# Schematic.net
KiCad netlist of a schematic drawn in Altium Designer
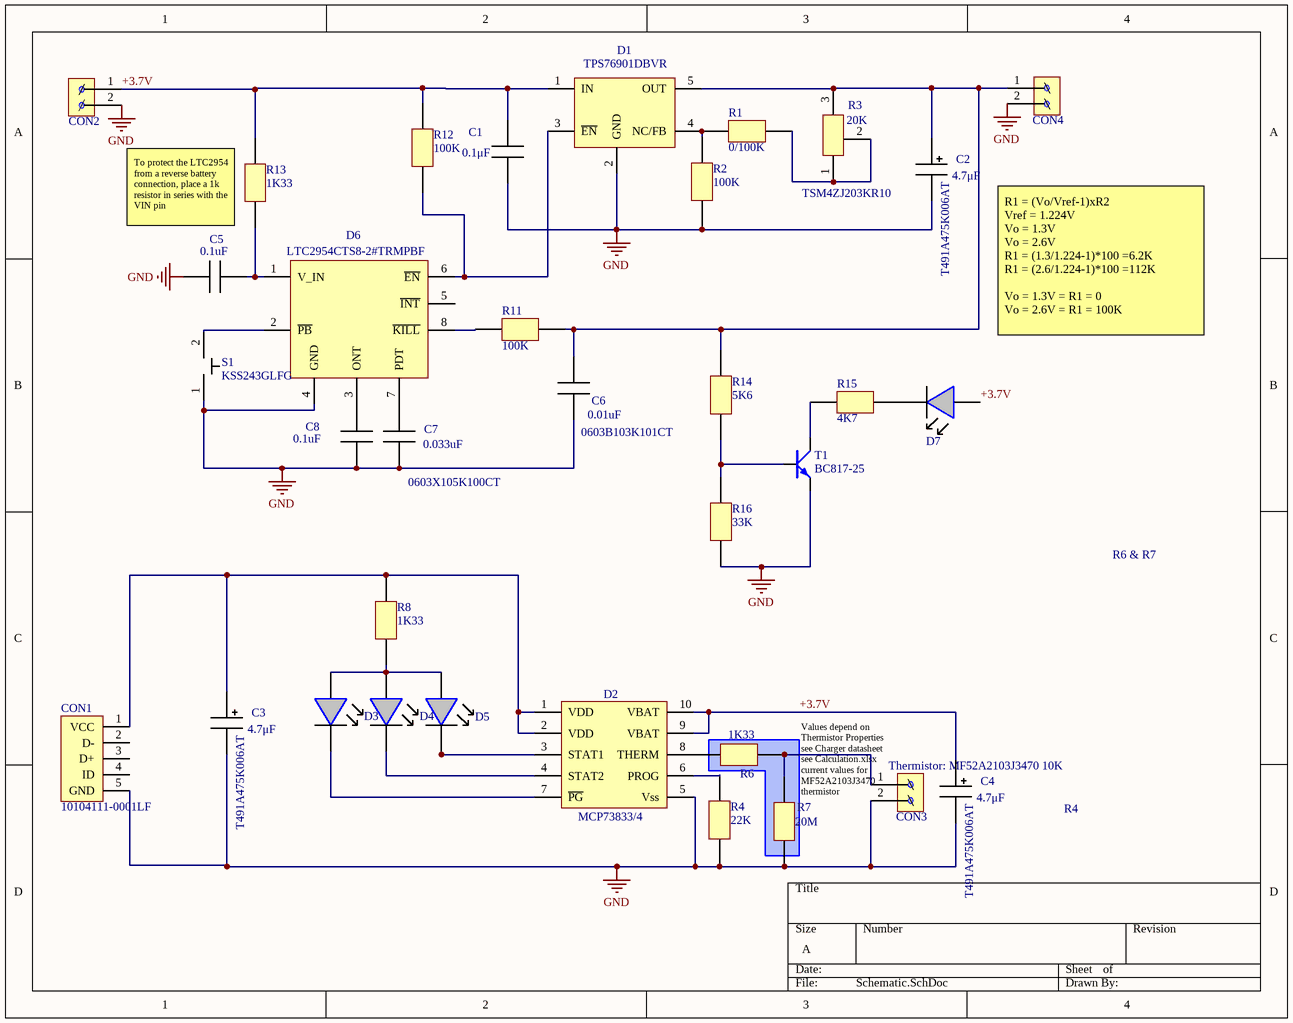
[diagram p0: Schematic.SchDoc]

(export (version "E")
  (design (tool "Eeschema 10.0.6"))
  (components
    (comp (ref "C1")
      (value "Capasitor")
      (footprint "CAPC1608X05N")
      (fields (field (name "CAPASITANCE") "0.1μF"))
      (libsource (lib "Componets") (part "Capasitor"))
    )
    (comp (ref "C2")
      (value "Capasitor_POL")
      (footprint "CAPMP3216X18N")
      (fields
        (field (name "CAPASITANCE") "4.7μF")
        (field (name "MANUFACTURER") "KEMET")
        (field (name "MANUFACTURERPN") "T491A475K006AT")
      )
      (libsource (lib "Componets") (part "Capasitor_POL"))
    )
    (comp (ref "C3")
      (value "Capasitor_POL")
      (footprint "CAPMP3216X18N")
      (fields
        (field (name "CAPASITANCE") "4.7μF")
        (field (name "MANUFACTURER") "KEMET")
        (field (name "MANUFACTURERPN") "T491A475K006AT")
      )
      (libsource (lib "Componets") (part "Capasitor_POL"))
    )
    (comp (ref "C4")
      (value "Capasitor_POL")
      (footprint "CAPMP3216X18N")
      (fields
        (field (name "CAPASITANCE") "4.7μF")
        (field (name "MANUFACTURER") "KEMET")
        (field (name "MANUFACTURERPN") "T491A475K006AT")
      )
      (libsource (lib "Componets") (part "Capasitor_POL"))
    )
    (comp (ref "C5")
      (value "Capasitor")
      (footprint "CAPC1608X05N")
      (fields (field (name "CAPASITANCE") "0.1uF"))
      (libsource (lib "Componets") (part "Capasitor"))
    )
    (comp (ref "C6")
      (value "Capasitor")
      (footprint "CAPC1608X05N")
      (fields
        (field (name "CAPASITANCE") "0.01uF")
        (field (name "MANUFACTURER") "WALSIN")
        (field (name "MANUFACTURERPN") "0603B103K101CT")
      )
      (libsource (lib "Componets") (part "Capasitor"))
    )
    (comp (ref "C7")
      (value "Capasitor")
      (footprint "CAPC1608X05N")
      (fields
        (field (name "CAPASITANCE") "0.033uF")
        (field (name "MANUFACTURER") "WALSIN")
        (field (name "MANUFACTURERPN") "0603X105K100CT")
      )
      (libsource (lib "Componets") (part "Capasitor"))
    )
    (comp (ref "C8")
      (value "Capasitor")
      (footprint "CAPC1608X05N")
      (fields (field (name "CAPASITANCE") "0.1uF"))
      (libsource (lib "Componets") (part "Capasitor"))
    )
    (comp (ref "CON1")
      (value "CON?")
      (footprint "MicroUSB")
      (fields (field (name "MANUFACTURER") "AMPHENOL FCI") (field (name "PARTNUMBER") "10104111-0001LF"))
      (libsource (lib "Componets") (part "MicroUSB"))
    )
    (comp (ref "CON2")
      (value "CON?")
      (footprint "HDR1X2_no_body")
      (libsource (lib "Componets") (part "HDR1X2"))
    )
    (comp (ref "CON3")
      (value "CON?")
      (footprint "HDR1X2_no_body")
      (fields (field (name "THERMISTOR") "MF52A2103J3470 10K"))
      (libsource (lib "") (part "HDR1X2_1"))
    )
    (comp (ref "CON4") (value "CON?") (footprint "HDR1X2_no_body") (libsource (lib "") (part "HDR1X2_1")))
    (comp (ref "D1")
      (value "D?")
      (footprint "SOT23-5AN")
      (fields (field (name "PARTNUMBER") "TPS76901DBVR"))
      (libsource (lib "Componets") (part "TPS76901"))
    )
    (comp (ref "D2")
      (value "MCP73833/4")
      (footprint "TSSOP50P490-10AN")
      (libsource (lib "Componets") (part "MCP73833/4"))
    )
    (comp (ref "D3") (value "LED") (footprint "CD1608-0603") (libsource (lib "Componets") (part "LED")))
    (comp (ref "D4") (value "LED") (footprint "CD1608-0603") (libsource (lib "Componets") (part "LED")))
    (comp (ref "D5") (value "LED") (footprint "CD1608-0603") (libsource (lib "Componets") (part "LED")))
    (comp (ref "D6")
      (value "D?")
      (footprint "TSOP65P280X100-8N")
      (fields (field (name "TEXASINSTRUMENTS") "LTC2954CTS8-2#TRMPBF"))
      (libsource (lib "Componets") (part "LTC2654-2"))
    )
    (comp (ref "D7") (value "LED") (footprint "CD1608-0603") (libsource (lib "Componets") (part "LED")))
    (comp (ref "R1")
      (value "R?")
      (footprint "RESC1608X04N")
      (fields (field (name "RESISTANCE") "0/100K"))
      (libsource (lib "") (part "Resistor_1"))
    )
    (comp (ref "R2")
      (value "R?")
      (footprint "RESC1608X04N")
      (fields (field (name "RESISTANCE") "100K"))
      (libsource (lib "Componets") (part "Resistor"))
    )
    (comp (ref "R3")
      (value "R?")
      (footprint "TSM4ZJ")
      (fields
        (field (name "RESISTANCE") "20K")
        (field (name "PARTNUMBER") "TSM4ZJ203KR10")
        (field (name "MANUFACTURER") "VISHAY")
      )
      (libsource (lib "Componets") (part "Resistor_ADJ"))
    )
    (comp (ref "R4")
      (value "R?")
      (footprint "RESC1608X04N")
      (fields (field (name "RESISTANCE") "22K"))
      (libsource (lib "Componets") (part "Resistor"))
    )
    (comp (ref "R6")
      (value "R?")
      (footprint "RESC1608X04N")
      (fields (field (name "RESISTANCE") "1K33"))
      (libsource (lib "") (part "Resistor_1"))
    )
    (comp (ref "R7")
      (value "R?")
      (footprint "RESC1608X04N")
      (fields (field (name "RESISTANCE") "20M"))
      (libsource (lib "Componets") (part "Resistor"))
    )
    (comp (ref "R8")
      (value "R?")
      (footprint "RESC1608X04N")
      (fields (field (name "RESISTANCE") "1K33"))
      (libsource (lib "Componets") (part "Resistor"))
    )
    (comp (ref "R11")
      (value "R?")
      (footprint "RESC1608X04N")
      (fields (field (name "RESISTANCE") "100K"))
      (libsource (lib "") (part "Resistor_1"))
    )
    (comp (ref "R12")
      (value "R?")
      (footprint "RESC1608X04N")
      (fields (field (name "RESISTANCE") "100K"))
      (libsource (lib "Componets") (part "Resistor"))
    )
    (comp (ref "R13")
      (value "R?")
      (footprint "RESC1608X04N")
      (fields (field (name "RESISTANCE") "1K33"))
      (libsource (lib "Componets") (part "Resistor"))
    )
    (comp (ref "R14")
      (value "R?")
      (footprint "RESC1608X04N")
      (fields (field (name "RESISTANCE") "5K6"))
      (libsource (lib "Componets") (part "Resistor"))
    )
    (comp (ref "R15")
      (value "R?")
      (footprint "RESC1608X04N")
      (fields (field (name "RESISTANCE") "4K7"))
      (libsource (lib "") (part "Resistor_1"))
    )
    (comp (ref "R16")
      (value "R?")
      (footprint "RESC1608X04N")
      (fields (field (name "RESISTANCE") "33K"))
      (libsource (lib "Componets") (part "Resistor"))
    )
    (comp (ref "S1")
      (value "S?")
      (footprint "KSS241")
      (fields (field (name "MANUFACTURER") "C and K components") (field (name "MANUFACTURERPN") "KSS243GLFG"))
      (libsource (lib "Componets") (part "PushButton"))
    )
    (comp (ref "T1")
      (value "BC817-25")
      (footprint "SOT323-3AM")
      (libsource (lib "Componets") (part "NPN SMD"))
    )
  )
  (nets
    (net (code "1") (name "/+3.7V") (class "Default")
      (node (ref "C1") (pin "1") (pinfunction "1_1") (pintype "passive"))
      (node (ref "C4") (pin "1") (pinfunction "1_1") (pintype "passive"))
      (node (ref "CON2") (pin "1") (pinfunction "1_1") (pintype "passive"))
      (node (ref "D1") (pin "1") (pinfunction "IN_1") (pintype "passive"))
      (node (ref "D2") (pin "10") (pinfunction "VBAT_10") (pintype "passive"))
      (node (ref "D2") (pin "9") (pinfunction "VBAT_9") (pintype "passive"))
      (node (ref "D7") (pin "1") (pinfunction "1_1") (pintype "passive"))
      (node (ref "R12") (pin "1") (pinfunction "1_1") (pintype "passive"))
      (node (ref "R13") (pin "1") (pinfunction "1_1") (pintype "passive"))
    )
    (net (code "2") (name "GND") (class "Default")
      (node (ref "C1") (pin "2") (pinfunction "2_2") (pintype "passive"))
      (node (ref "C2") (pin "2") (pinfunction "2_2") (pintype "passive"))
      (node (ref "C3") (pin "2") (pinfunction "2_2") (pintype "passive"))
      (node (ref "C4") (pin "2") (pinfunction "2_2") (pintype "passive"))
      (node (ref "C5") (pin "2") (pinfunction "2_2") (pintype "passive"))
      (node (ref "C6") (pin "2") (pinfunction "2_2") (pintype "passive"))
      (node (ref "C7") (pin "2") (pinfunction "2_2") (pintype "passive"))
      (node (ref "C8") (pin "2") (pinfunction "2_2") (pintype "passive"))
      (node (ref "CON1") (pin "5") (pinfunction "GND_5") (pintype "passive"))
      (node (ref "CON2") (pin "2") (pinfunction "2_2") (pintype "passive"))
      (node (ref "CON3") (pin "2") (pinfunction "2_2") (pintype "passive"))
      (node (ref "CON4") (pin "2") (pinfunction "2_2") (pintype "passive"))
      (node (ref "D1") (pin "2") (pinfunction "GND_2") (pintype "passive"))
      (node (ref "D2") (pin "5") (pinfunction "Vss_5") (pintype "passive"))
      (node (ref "D6") (pin "4") (pinfunction "GND_4") (pintype "passive"))
      (node (ref "R16") (pin "2") (pinfunction "2_2") (pintype "passive"))
      (node (ref "R2") (pin "2") (pinfunction "2_2") (pintype "passive"))
      (node (ref "R4") (pin "2") (pinfunction "2_2") (pintype "passive"))
      (node (ref "R7") (pin "2") (pinfunction "2_2") (pintype "passive"))
      (node (ref "S1") (pin "1") (pinfunction "1_1") (pintype "passive"))
      (node (ref "T1") (pin "2") (pinfunction "E_2") (pintype "passive"))
    )
    (net (code "3") (name "Net-(CON1-VCC)") (class "Default")
      (node (ref "C3") (pin "1") (pinfunction "1_1") (pintype "passive"))
      (node (ref "CON1") (pin "1") (pinfunction "VCC_1") (pintype "passive"))
      (node (ref "D2") (pin "1") (pinfunction "VDD_1") (pintype "passive"))
      (node (ref "D2") (pin "2") (pinfunction "VDD_2") (pintype "passive"))
      (node (ref "R8") (pin "1") (pinfunction "1_1") (pintype "passive"))
    )
    (net (code "4") (name "Net-(CON3-Pad1)") (class "Default")
      (node (ref "CON3") (pin "1") (pinfunction "1_1") (pintype "passive"))
      (node (ref "R6") (pin "2") (pinfunction "2_2") (pintype "passive"))
      (node (ref "R7") (pin "1") (pinfunction "1_1") (pintype "passive"))
    )
    (net (code "5") (name "Net-(D1-NC{slash}FB)") (class "Default")
      (node (ref "D1") (pin "4") (pinfunction "NC/FB_4") (pintype "passive"))
      (node (ref "R1") (pin "1") (pinfunction "1_1") (pintype "passive"))
      (node (ref "R2") (pin "1") (pinfunction "1_1") (pintype "passive"))
    )
    (net (code "6") (name "Net-(D1-OUT)") (class "Default")
      (node (ref "C2") (pin "1") (pinfunction "1_1") (pintype "passive"))
      (node (ref "C6") (pin "1") (pinfunction "1_1") (pintype "passive"))
      (node (ref "CON4") (pin "1") (pinfunction "1_1") (pintype "passive"))
      (node (ref "D1") (pin "5") (pinfunction "OUT_5") (pintype "passive"))
      (node (ref "R11") (pin "2") (pinfunction "2_2") (pintype "passive"))
      (node (ref "R14") (pin "1") (pinfunction "1_1") (pintype "passive"))
      (node (ref "R3") (pin "3") (pinfunction "3_3") (pintype "passive"))
    )
    (net (code "7") (name "Net-(D1-~{EN})") (class "Default")
      (node (ref "D1") (pin "3") (pinfunction "~{EN}_3") (pintype "passive"))
      (node (ref "D6") (pin "6") (pinfunction "~{EN}_6") (pintype "passive"))
      (node (ref "R12") (pin "2") (pinfunction "2_2") (pintype "passive"))
    )
    (net (code "8") (name "Net-(D2-PROG)") (class "Default")
      (node (ref "D2") (pin "6") (pinfunction "PROG_6") (pintype "passive"))
      (node (ref "R4") (pin "1") (pinfunction "1_1") (pintype "passive"))
    )
    (net (code "9") (name "Net-(D2-STAT1)") (class "Default")
      (node (ref "D2") (pin "3") (pinfunction "STAT1_3") (pintype "passive"))
      (node (ref "D5") (pin "2") (pinfunction "2_2") (pintype "passive"))
    )
    (net (code "10") (name "Net-(D2-STAT2)") (class "Default")
      (node (ref "D2") (pin "4") (pinfunction "STAT2_4") (pintype "passive"))
      (node (ref "D4") (pin "2") (pinfunction "2_2") (pintype "passive"))
    )
    (net (code "11") (name "Net-(D2-THERM)") (class "Default")
      (node (ref "D2") (pin "8") (pinfunction "THERM_8") (pintype "passive"))
      (node (ref "R6") (pin "1") (pinfunction "1_1") (pintype "passive"))
    )
    (net (code "12") (name "Net-(D2-~{PG})") (class "Default")
      (node (ref "D2") (pin "7") (pinfunction "~{PG}_7") (pintype "passive"))
      (node (ref "D3") (pin "2") (pinfunction "2_2") (pintype "passive"))
    )
    (net (code "13") (name "Net-(D3-Pad1)") (class "Default")
      (node (ref "D3") (pin "1") (pinfunction "1_1") (pintype "passive"))
      (node (ref "D4") (pin "1") (pinfunction "1_1") (pintype "passive"))
      (node (ref "D5") (pin "1") (pinfunction "1_1") (pintype "passive"))
      (node (ref "R8") (pin "2") (pinfunction "2_2") (pintype "passive"))
    )
    (net (code "14") (name "Net-(D6-ONT)") (class "Default")
      (node (ref "C8") (pin "1") (pinfunction "1_1") (pintype "passive"))
      (node (ref "D6") (pin "3") (pinfunction "ONT_3") (pintype "passive"))
    )
    (net (code "15") (name "Net-(D6-PDT)") (class "Default")
      (node (ref "C7") (pin "1") (pinfunction "1_1") (pintype "passive"))
      (node (ref "D6") (pin "7") (pinfunction "PDT_7") (pintype "passive"))
    )
    (net (code "16") (name "Net-(D6-V_IN)") (class "Default")
      (node (ref "C5") (pin "1") (pinfunction "1_1") (pintype "passive"))
      (node (ref "D6") (pin "1") (pinfunction "V_IN_1") (pintype "passive"))
      (node (ref "R13") (pin "2") (pinfunction "2_2") (pintype "passive"))
    )
    (net (code "17") (name "Net-(D6-~{KILL})") (class "Default")
      (node (ref "D6") (pin "8") (pinfunction "~{KILL}_8") (pintype "passive"))
      (node (ref "R11") (pin "1") (pinfunction "1_1") (pintype "passive"))
    )
    (net (code "18") (name "Net-(D6-~{PB})") (class "Default")
      (node (ref "D6") (pin "2") (pinfunction "~{PB}_2") (pintype "passive"))
      (node (ref "S1") (pin "2") (pinfunction "2_2") (pintype "passive"))
    )
    (net (code "19") (name "Net-(D7-Pad2)") (class "Default")
      (node (ref "D7") (pin "2") (pinfunction "2_2") (pintype "passive"))
      (node (ref "R15") (pin "2") (pinfunction "2_2") (pintype "passive"))
    )
    (net (code "20") (name "Net-(R1-Pad2)") (class "Default")
      (node (ref "R1") (pin "2") (pinfunction "2_2") (pintype "passive"))
      (node (ref "R3") (pin "1") (pinfunction "1_1") (pintype "passive"))
      (node (ref "R3") (pin "2") (pinfunction "2_2") (pintype "passive"))
    )
    (net (code "21") (name "Net-(T1-B)") (class "Default")
      (node (ref "R14") (pin "2") (pinfunction "2_2") (pintype "passive"))
      (node (ref "R16") (pin "1") (pinfunction "1_1") (pintype "passive"))
      (node (ref "T1") (pin "1") (pinfunction "B_1") (pintype "passive"))
    )
    (net (code "22") (name "Net-(T1-C)") (class "Default")
      (node (ref "R15") (pin "1") (pinfunction "1_1") (pintype "passive"))
      (node (ref "T1") (pin "3") (pinfunction "C_3") (pintype "passive"))
    )
    (net (code "23") (name "unconnected-(CON1-D+-Pad3)") (class "Default")
      (node (ref "CON1") (pin "3") (pinfunction "D+_3") (pintype "passive"))
    )
    (net (code "24") (name "unconnected-(CON1-D--Pad2)") (class "Default")
      (node (ref "CON1") (pin "2") (pinfunction "D-_2") (pintype "passive"))
    )
    (net (code "25") (name "unconnected-(CON1-ID-Pad4)") (class "Default")
      (node (ref "CON1") (pin "4") (pinfunction "ID_4") (pintype "passive"))
    )
    (net (code "26") (name "unconnected-(D6-~{INT}-Pad5)") (class "Default")
      (node (ref "D6") (pin "5") (pinfunction "~{INT}_5") (pintype "passive"))
    )
  )
)
